# gsm.net
KiCad netlist of a schematic drawn in Altium Designer
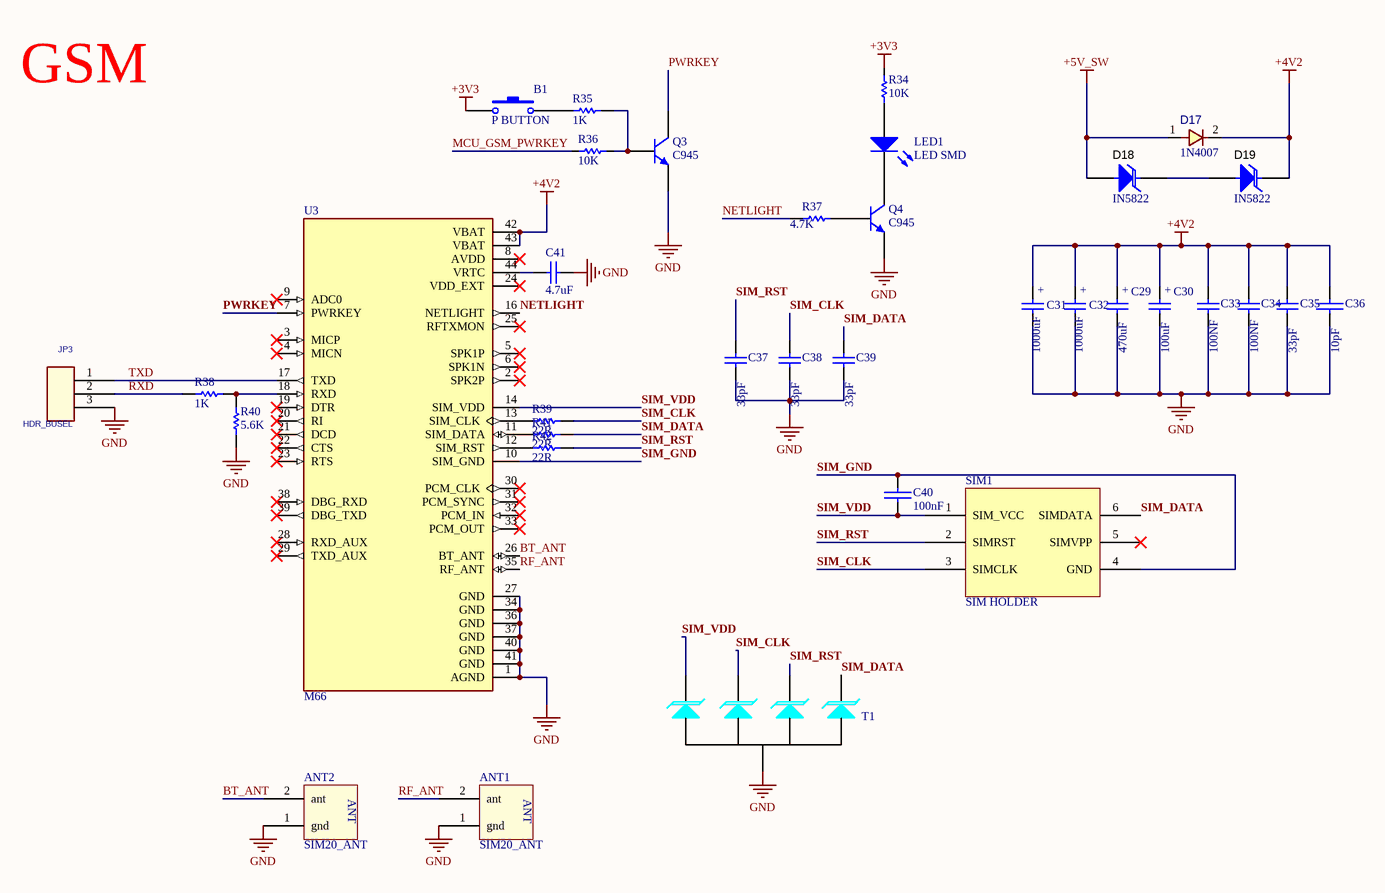
[diagram p0: gsm.SchDoc]

(export (version "E")
  (design (tool "Eeschema 10.0.6"))
  (components
    (comp (ref "ANT1")
      (value "SIM20_ANT")
      (footprint "MY_SIM20_ANT")
      (description "ANT")
      (libsource (lib "altium-import") (part "root_2_SIM20_ANT_"))
    )
    (comp (ref "ANT2")
      (value "SIM20_ANT")
      (footprint "MY_SIM20_ANT")
      (description "ANT")
      (libsource (lib "altium-import") (part "root_2_SIM20_ANT_"))
    )
    (comp (ref "B1")
      (value "P BUTTON")
      (footprint "MY_SPST-0.5")
      (libsource (lib "AMINLIB") (part "PUSH BUTTON_SMALL"))
    )
    (comp (ref "C29")
      (value "470uF")
      (footprint "MY_Cap1000u -smd")
      (description "aluminium")
      (libsource (lib "AMINLIB") (part "cap_smd_1000u_smd G"))
    )
    (comp (ref "C30")
      (value "100uF")
      (footprint "MY_Cap1000u -smd")
      (description "aluminium")
      (libsource (lib "AMINLIB") (part "cap_smd_1000u_smd G"))
    )
    (comp (ref "C31")
      (value "1000uF")
      (footprint "MY_CAP_SMD-C")
      (description "6X3.2MM")
      (libsource (lib "altium-import") (part "root_3_CAP_TANTAL_C_"))
    )
    (comp (ref "C32")
      (value "1000uF")
      (footprint "MY_CAP_SMD-C")
      (description "6X3.2MM")
      (libsource (lib "altium-import") (part "root_3_CAP_TANTAL_C_"))
    )
    (comp (ref "C33")
      (value "100NF")
      (footprint "CAP0603")
      (description "TOTAL CAPACITOR SMD PACK")
      (fields (field (name "DESIGNER") "Abbas Basereh"))
      (libsource (lib "Altium") (part "CAP SMD PACKAGE"))
    )
    (comp (ref "C34")
      (value "100NF")
      (footprint "CAP0603")
      (description "TOTAL CAPACITOR SMD PACK")
      (fields (field (name "DESIGNER") "Abbas Basereh"))
      (libsource (lib "Altium") (part "CAP SMD PACKAGE"))
    )
    (comp (ref "C35")
      (value "33pF")
      (footprint "CAP0603")
      (description "TOTAL CAPACITOR SMD PACK")
      (fields (field (name "DESIGNER") "Abbas Basereh"))
      (libsource (lib "Altium") (part "CAP SMD PACKAGE"))
    )
    (comp (ref "C36")
      (value "10pF")
      (footprint "Cap-0603")
      (description "Capacitor")
      (fields (field (name "PUBLISHER") "Altium Limited"))
      (libsource (lib "A.Mohebbi") (part "Capacitor."))
    )
    (comp (ref "C37")
      (value "33pF")
      (footprint "CAP0603")
      (description "TOTAL CAPACITOR SMD PACK")
      (fields (field (name "DESIGNER") "Abbas Basereh"))
      (libsource (lib "Altium") (part "CAP SMD PACKAGE"))
    )
    (comp (ref "C38")
      (value "33pF")
      (footprint "CAP0603")
      (description "TOTAL CAPACITOR SMD PACK")
      (fields (field (name "DESIGNER") "Abbas Basereh"))
      (libsource (lib "Altium") (part "CAP SMD PACKAGE"))
    )
    (comp (ref "C39")
      (value "33pF")
      (footprint "CAP0603")
      (description "TOTAL CAPACITOR SMD PACK")
      (fields (field (name "DESIGNER") "Abbas Basereh"))
      (libsource (lib "Altium") (part "CAP SMD PACKAGE"))
    )
    (comp (ref "C40")
      (value "100nF")
      (footprint "Cap-0805")
      (description "Capacitor")
      (fields (field (name "PUBLISHER") "Altium Limited"))
      (libsource (lib "altium-import") (part "root_0_Capacitor._"))
    )
    (comp (ref "C41")
      (value "4.7uF")
      (footprint "CAPC3413X12N")
      (description "CAP 0805")
      (fields (field (name "DESIGNER") "Abbas Basereh"))
      (libsource (lib "2017AbbasBasereh9365731239 -ver1") (part "CAP SMD 0805"))
    )
    (comp (ref "D17")
      (value "1N4007")
      (footprint "D_SMA")
      (description "DIODE, GENERAL PURPOSE, 1000V/1A")
      (fields (field (name "Comment") "1N4007 SMD M7"))
      (libsource (lib "Diode") (part "1N4007 SMD M7"))
    )
    (comp (ref "D18")
      (value "IN5822")
      (footprint "BYW98")
      (description "Diode, , 20 - 40V, 3.0 A")
      (fields (field (name "Comment") "IN5822 THD"))
      (libsource (lib "altium-import") (part "root_2_IN5822 THD_"))
    )
    (comp (ref "D19")
      (value "IN5822")
      (footprint "BYW98")
      (description "Diode, , 20 - 40V, 3.0 A")
      (fields (field (name "Comment") "IN5822 THD"))
      (libsource (lib "altium-import") (part "root_2_IN5822 THD_"))
    )
    (comp (ref "JP3")
      (value "HDR_BUSEL")
      (footprint "HDR_1x3")
      (description "header or jumper box")
      (libsource (lib "2017AbbasBasereh9365731239 -ver1") (part "Header 1x3"))
    )
    (comp (ref "LED1")
      (value "LED SMD")
      (footprint "MY_LED_SMD")
      (libsource (lib "AMINLIB") (part "LED SMD"))
    )
    (comp (ref "Q3")
      (value "C945")
      (footprint "SOT23_N")
      (description "NPN Silicon Epitaxial Planar Transistor")
      (fields (field (name "PUBLISHER") "Abbas Basereh"))
      (libsource (lib "2017AbbasBasereh9365731239 -ver1") (part "C945"))
    )
    (comp (ref "Q4")
      (value "C945")
      (footprint "SOT23_N")
      (description "NPN Silicon Epitaxial Planar Transistor")
      (fields (field (name "PUBLISHER") "Abbas Basereh"))
      (libsource (lib "2017AbbasBasereh9365731239 -ver1") (part "C945"))
    )
    (comp (ref "R34")
      (value "10K")
      (footprint "RES 0603 (1608X06L)")
      (description "Resistor")
      (fields (field (name "TOLERANCE") "5%") (field (name "POWER") "1/4 W"))
      (libsource (lib "altium-import") (part "root_1_Resistor_"))
    )
    (comp (ref "R35")
      (value "1K")
      (footprint "Resistor_SMD_1206 (3216)")
      (description "Resistor")
      (fields (field (name "PUBLISHER") "Seyed Razi Vesali") (field (name "EMAIL") "razi.vesali@gmail.com"))
      (libsource (lib "resistors") (part "Resistor"))
    )
    (comp (ref "R36")
      (value "10K")
      (footprint "RES 0603 (1608X06L)")
      (description "Resistor")
      (fields (field (name "TOLERANCE") "5%") (field (name "POWER") "1/4 W"))
      (libsource (lib "altium-import") (part "root_0_Resistor_"))
    )
    (comp (ref "R37")
      (value "4.7K")
      (footprint "Resistor_SMD_1206")
      (description "Resistor 0.25w")
      (fields (field (name "PUBLISHER") "Altium Limited"))
      (libsource (lib "A.Mohebbi") (part "Resistor"))
    )
    (comp (ref "R38")
      (value "1K")
      (footprint "Resistor_SMD_1206 (3216)")
      (description "Resistor")
      (fields (field (name "PUBLISHER") "Seyed Razi Vesali") (field (name "EMAIL") "razi.vesali@gmail.com"))
      (libsource (lib "resistors") (part "Resistor"))
    )
    (comp (ref "R39")
      (value "22R")
      (footprint "Resistor_SMD_0603 (1608)")
      (description "Resistor")
      (fields (field (name "PUBLISHER") "Seyed Razi Vesali") (field (name "EMAIL") "razi.vesali@gmail.com"))
      (libsource (lib "resistors") (part "Resistor"))
    )
    (comp (ref "R40")
      (value "5.6K")
      (footprint "Resistor_SMD_0805 (2012)")
      (description "Resistor")
      (fields (field (name "PUBLISHER") "Seyed Razi Vesali") (field (name "EMAIL") "razi.vesali@gmail.com"))
      (libsource (lib "resistors") (part "Resistor"))
    )
    (comp (ref "R41")
      (value "22R")
      (footprint "Resistor_SMD_0603 (1608)")
      (description "Resistor")
      (fields (field (name "PUBLISHER") "Seyed Razi Vesali") (field (name "EMAIL") "razi.vesali@gmail.com"))
      (libsource (lib "resistors") (part "Resistor"))
    )
    (comp (ref "R42")
      (value "22R")
      (footprint "Resistor_SMD_0603 (1608)")
      (description "Resistor")
      (fields (field (name "PUBLISHER") "Seyed Razi Vesali") (field (name "EMAIL") "razi.vesali@gmail.com"))
      (libsource (lib "resistors") (part "Resistor"))
    )
    (comp (ref "SIM1")
      (value "SIM HOLDER")
      (footprint "SIM HOLDER 6")
      (libsource (lib "altium-import") (part "root_0_SIM HOLDER_"))
    )
    (comp (ref "T1")
      (value "TVS (SMF05)")
      (footprint "SC70-5L")
      (description "SMF05 and SMF12  TVS Diode Array  For ESD and Latch-Up Protection")
      (libsource (lib "altium-import") (part "root_0_TVS (SMF05)_"))
    )
    (comp (ref "U3")
      (value "M66")
      (footprint "XCVR_M66")
      (fields (field (name "MF") "Quectel"))
      (libsource (lib "M66") (part "M66"))
    )
  )
  (nets
    (net (code "1") (name "+3V3") (class "Default")
      (node (ref "B1") (pin "1") (pinfunction "1_1") (pintype "passive"))
      (node (ref "R34") (pin "2") (pinfunction "2_2") (pintype "passive"))
    )
    (net (code "2") (name "+4V2") (class "Default")
      (node (ref "C29") (pin "+") (pinfunction "+_+") (pintype "passive"))
      (node (ref "C30") (pin "+") (pinfunction "+_+") (pintype "passive"))
      (node (ref "C31") (pin "+") (pinfunction "+_+") (pintype "passive"))
      (node (ref "C32") (pin "+") (pinfunction "+_+") (pintype "passive"))
      (node (ref "C33") (pin "2") (pinfunction "2_2") (pintype "passive"))
      (node (ref "C34") (pin "2") (pinfunction "2_2") (pintype "passive"))
      (node (ref "C35") (pin "2") (pinfunction "2_2") (pintype "passive"))
      (node (ref "C36") (pin "1") (pinfunction "1_1") (pintype "passive"))
      (node (ref "D17") (pin "2") (pinfunction "2_2") (pintype "passive"))
      (node (ref "D19") (pin "2") (pinfunction "K_2") (pintype "passive"))
      (node (ref "U3") (pin "42") (pinfunction "VBAT_42") (pintype "power_in"))
      (node (ref "U3") (pin "43") (pinfunction "VBAT_43") (pintype "power_in"))
    )
    (net (code "3") (name "+5V_SW") (class "Default")
      (node (ref "D17") (pin "1") (pinfunction "1_1") (pintype "passive"))
      (node (ref "D18") (pin "1") (pinfunction "A_1") (pintype "passive"))
    )
    (net (code "4") (name "/BT_ANT") (class "Default")
      (node (ref "ANT2") (pin "2") (pinfunction "ant_2") (pintype "passive"))
      (node (ref "U3") (pin "26") (pinfunction "BT_ANT_26") (pintype "bidirectional"))
    )
    (net (code "5") (name "/MCU_GSM_PWRKEY") (class "Default")
      (node (ref "R36") (pin "1") (pinfunction "1_1") (pintype "passive"))
    )
    (net (code "6") (name "/NETLIGHT") (class "Default")
      (node (ref "R37") (pin "1") (pinfunction "1_1") (pintype "passive"))
      (node (ref "U3") (pin "16") (pinfunction "NETLIGHT_16") (pintype "output"))
    )
    (net (code "7") (name "/PWRKEY") (class "Default")
      (node (ref "Q3") (pin "3") (pinfunction "C_3") (pintype "passive"))
      (node (ref "U3") (pin "7") (pinfunction "PWRKEY_7") (pintype "input"))
    )
    (net (code "8") (name "/RF_ANT") (class "Default")
      (node (ref "ANT1") (pin "2") (pinfunction "ant_2") (pintype "passive"))
      (node (ref "U3") (pin "35") (pinfunction "RF_ANT_35") (pintype "bidirectional"))
    )
    (net (code "9") (name "/RXD") (class "Default")
      (node (ref "JP3") (pin "2") (pinfunction "2_2") (pintype "passive"))
      (node (ref "R38") (pin "1") (pinfunction "1_1") (pintype "passive"))
    )
    (net (code "10") (name "/SIM_CLK") (class "Default")
      (node (ref "C38") (pin "2") (pinfunction "2_2") (pintype "passive"))
      (node (ref "R39") (pin "2") (pinfunction "2_2") (pintype "passive"))
      (node (ref "SIM1") (pin "3") (pinfunction "SIMCLK_3") (pintype "passive"))
      (node (ref "T1") (pin "3") (pinfunction "K_3") (pintype "passive"))
    )
    (net (code "11") (name "/SIM_DATA") (class "Default")
      (node (ref "C39") (pin "2") (pinfunction "2_2") (pintype "passive"))
      (node (ref "R41") (pin "2") (pinfunction "2_2") (pintype "passive"))
      (node (ref "SIM1") (pin "6") (pinfunction "SIMDATA_6") (pintype "passive"))
      (node (ref "T1") (pin "5") (pinfunction "K_5") (pintype "passive"))
    )
    (net (code "12") (name "/SIM_GND") (class "Default")
      (node (ref "C40") (pin "1") (pinfunction "1_1") (pintype "passive"))
      (node (ref "SIM1") (pin "4") (pinfunction "GND_4") (pintype "passive"))
      (node (ref "U3") (pin "10") (pinfunction "SIM_GND_10") (pintype "power_in"))
    )
    (net (code "13") (name "/SIM_RST") (class "Default")
      (node (ref "C37") (pin "2") (pinfunction "2_2") (pintype "passive"))
      (node (ref "R42") (pin "2") (pinfunction "2_2") (pintype "passive"))
      (node (ref "SIM1") (pin "2") (pinfunction "SIMRST_2") (pintype "passive"))
      (node (ref "T1") (pin "4") (pinfunction "K_4") (pintype "passive"))
    )
    (net (code "14") (name "/SIM_VDD") (class "Default")
      (node (ref "C40") (pin "2") (pinfunction "2_2") (pintype "passive"))
      (node (ref "SIM1") (pin "1") (pinfunction "SIM_VCC_1") (pintype "passive"))
      (node (ref "T1") (pin "1") (pinfunction "K_1") (pintype "passive"))
      (node (ref "U3") (pin "14") (pinfunction "SIM_VDD_14") (pintype "power_in"))
    )
    (net (code "15") (name "/TXD") (class "Default")
      (node (ref "JP3") (pin "1") (pinfunction "1_1") (pintype "passive"))
      (node (ref "U3") (pin "17") (pinfunction "TXD_17") (pintype "output"))
    )
    (net (code "16") (name "GND") (class "Default")
      (node (ref "ANT1") (pin "1") (pinfunction "gnd_1") (pintype "passive"))
      (node (ref "ANT2") (pin "1") (pinfunction "gnd_1") (pintype "passive"))
      (node (ref "C29") (pin "-") (pinfunction "-_-") (pintype "passive"))
      (node (ref "C30") (pin "-") (pinfunction "-_-") (pintype "passive"))
      (node (ref "C31") (pin "-") (pinfunction "-_-") (pintype "passive"))
      (node (ref "C32") (pin "-") (pinfunction "-_-") (pintype "passive"))
      (node (ref "C33") (pin "1") (pinfunction "1_1") (pintype "passive"))
      (node (ref "C34") (pin "1") (pinfunction "1_1") (pintype "passive"))
      (node (ref "C35") (pin "1") (pinfunction "1_1") (pintype "passive"))
      (node (ref "C36") (pin "2") (pinfunction "2_2") (pintype "passive"))
      (node (ref "C37") (pin "1") (pinfunction "1_1") (pintype "passive"))
      (node (ref "C38") (pin "1") (pinfunction "1_1") (pintype "passive"))
      (node (ref "C39") (pin "1") (pinfunction "1_1") (pintype "passive"))
      (node (ref "C41") (pin "2") (pinfunction "2_2") (pintype "passive"))
      (node (ref "JP3") (pin "3") (pinfunction "3_3") (pintype "passive"))
      (node (ref "Q3") (pin "2") (pinfunction "E_2") (pintype "passive"))
      (node (ref "Q4") (pin "2") (pinfunction "E_2") (pintype "passive"))
      (node (ref "R40") (pin "1") (pinfunction "1_1") (pintype "passive"))
      (node (ref "T1") (pin "2") (pinfunction "A_2") (pintype "passive"))
      (node (ref "U3") (pin "1") (pinfunction "AGND_1") (pintype "power_in"))
      (node (ref "U3") (pin "27") (pinfunction "GND_27") (pintype "power_in"))
      (node (ref "U3") (pin "34") (pinfunction "GND_34") (pintype "power_in"))
      (node (ref "U3") (pin "36") (pinfunction "GND_36") (pintype "power_in"))
      (node (ref "U3") (pin "37") (pinfunction "GND_37") (pintype "power_in"))
      (node (ref "U3") (pin "40") (pinfunction "GND_40") (pintype "power_in"))
      (node (ref "U3") (pin "41") (pinfunction "GND_41") (pintype "power_in"))
    )
    (net (code "17") (name "Net-(B1-Pad2)") (class "Default")
      (node (ref "B1") (pin "2") (pinfunction "2_2") (pintype "passive"))
      (node (ref "R35") (pin "1") (pinfunction "1_1") (pintype "passive"))
    )
    (net (code "18") (name "Net-(D18-K)") (class "Default")
      (node (ref "D18") (pin "2") (pinfunction "K_2") (pintype "passive"))
      (node (ref "D19") (pin "1") (pinfunction "A_1") (pintype "passive"))
    )
    (net (code "19") (name "Net-(LED1-A)") (class "Default")
      (node (ref "LED1") (pin "1") (pinfunction "A_1") (pintype "passive"))
      (node (ref "R34") (pin "1") (pinfunction "1_1") (pintype "passive"))
    )
    (net (code "20") (name "Net-(LED1-K)") (class "Default")
      (node (ref "LED1") (pin "2") (pinfunction "K_2") (pintype "passive"))
      (node (ref "Q4") (pin "3") (pinfunction "C_3") (pintype "passive"))
    )
    (net (code "21") (name "Net-(Q3-B)") (class "Default")
      (node (ref "Q3") (pin "1") (pinfunction "B_1") (pintype "passive"))
      (node (ref "R35") (pin "2") (pinfunction "2_2") (pintype "passive"))
      (node (ref "R36") (pin "2") (pinfunction "2_2") (pintype "passive"))
    )
    (net (code "22") (name "Net-(Q4-B)") (class "Default")
      (node (ref "Q4") (pin "1") (pinfunction "B_1") (pintype "passive"))
      (node (ref "R37") (pin "2") (pinfunction "2_2") (pintype "passive"))
    )
    (net (code "23") (name "Net-(U3-RXD)") (class "Default")
      (node (ref "R38") (pin "2") (pinfunction "2_2") (pintype "passive"))
      (node (ref "R40") (pin "2") (pinfunction "2_2") (pintype "passive"))
      (node (ref "U3") (pin "18") (pinfunction "RXD_18") (pintype "input"))
    )
    (net (code "24") (name "Net-(U3-SIM_CLK)") (class "Default")
      (node (ref "R39") (pin "1") (pinfunction "1_1") (pintype "passive"))
      (node (ref "U3") (pin "13") (pinfunction "SIM_CLK_13") (pintype "output"))
    )
    (net (code "25") (name "Net-(U3-SIM_DATA)") (class "Default")
      (node (ref "R41") (pin "1") (pinfunction "1_1") (pintype "passive"))
      (node (ref "U3") (pin "11") (pinfunction "SIM_DATA_11") (pintype "bidirectional"))
    )
    (net (code "26") (name "Net-(U3-SIM_RST)") (class "Default")
      (node (ref "R42") (pin "1") (pinfunction "1_1") (pintype "passive"))
      (node (ref "U3") (pin "12") (pinfunction "SIM_RST_12") (pintype "output"))
    )
    (net (code "27") (name "Net-(U3-VRTC)") (class "Default")
      (node (ref "C41") (pin "1") (pinfunction "1_1") (pintype "passive"))
      (node (ref "U3") (pin "44") (pinfunction "VRTC_44") (pintype "power_in"))
    )
    (net (code "28") (name "unconnected-(SIM1-SIMVPP-Pad5)") (class "Default")
      (node (ref "SIM1") (pin "5") (pinfunction "SIMVPP_5") (pintype "passive+no_connect"))
    )
    (net (code "29") (name "unconnected-(U3-ADC0-Pad9)") (class "Default")
      (node (ref "U3") (pin "9") (pinfunction "ADC0_9") (pintype "input+no_connect"))
    )
    (net (code "30") (name "unconnected-(U3-AVDD-Pad8)") (class "Default")
      (node (ref "U3") (pin "8") (pinfunction "AVDD_8") (pintype "power_in+no_connect"))
    )
    (net (code "31") (name "unconnected-(U3-CTS-Pad22)") (class "Default")
      (node (ref "U3") (pin "22") (pinfunction "CTS_22") (pintype "output+no_connect"))
    )
    (net (code "32") (name "unconnected-(U3-DBG_RXD-Pad38)") (class "Default")
      (node (ref "U3") (pin "38") (pinfunction "DBG_RXD_38") (pintype "input+no_connect"))
    )
    (net (code "33") (name "unconnected-(U3-DBG_TXD-Pad39)") (class "Default")
      (node (ref "U3") (pin "39") (pinfunction "DBG_TXD_39") (pintype "output+no_connect"))
    )
    (net (code "34") (name "unconnected-(U3-DCD-Pad21)") (class "Default")
      (node (ref "U3") (pin "21") (pinfunction "DCD_21") (pintype "output+no_connect"))
    )
    (net (code "35") (name "unconnected-(U3-DTR-Pad19)") (class "Default")
      (node (ref "U3") (pin "19") (pinfunction "DTR_19") (pintype "input+no_connect"))
    )
    (net (code "36") (name "unconnected-(U3-MICN-Pad4)") (class "Default")
      (node (ref "U3") (pin "4") (pinfunction "MICN_4") (pintype "input+no_connect"))
    )
    (net (code "37") (name "unconnected-(U3-MICP-Pad3)") (class "Default")
      (node (ref "U3") (pin "3") (pinfunction "MICP_3") (pintype "input+no_connect"))
    )
    (net (code "38") (name "unconnected-(U3-PCM_CLK-Pad30)") (class "Default")
      (node (ref "U3") (pin "30") (pinfunction "PCM_CLK_30") (pintype "output+no_connect"))
    )
    (net (code "39") (name "unconnected-(U3-PCM_IN-Pad32)") (class "Default")
      (node (ref "U3") (pin "32") (pinfunction "PCM_IN_32") (pintype "input+no_connect"))
    )
    (net (code "40") (name "unconnected-(U3-PCM_OUT-Pad33)") (class "Default")
      (node (ref "U3") (pin "33") (pinfunction "PCM_OUT_33") (pintype "output+no_connect"))
    )
    (net (code "41") (name "unconnected-(U3-PCM_SYNC-Pad31)") (class "Default")
      (node (ref "U3") (pin "31") (pinfunction "PCM_SYNC_31") (pintype "output+no_connect"))
    )
    (net (code "42") (name "unconnected-(U3-RFTXMON-Pad25)") (class "Default")
      (node (ref "U3") (pin "25") (pinfunction "RFTXMON_25") (pintype "output+no_connect"))
    )
    (net (code "43") (name "unconnected-(U3-RI-Pad20)") (class "Default")
      (node (ref "U3") (pin "20") (pinfunction "RI_20") (pintype "output+no_connect"))
    )
    (net (code "44") (name "unconnected-(U3-RTS-Pad23)") (class "Default")
      (node (ref "U3") (pin "23") (pinfunction "RTS_23") (pintype "input+no_connect"))
    )
    (net (code "45") (name "unconnected-(U3-RXD_AUX-Pad28)") (class "Default")
      (node (ref "U3") (pin "28") (pinfunction "RXD_AUX_28") (pintype "input+no_connect"))
    )
    (net (code "46") (name "unconnected-(U3-SPK1N-Pad6)") (class "Default")
      (node (ref "U3") (pin "6") (pinfunction "SPK1N_6") (pintype "output+no_connect"))
    )
    (net (code "47") (name "unconnected-(U3-SPK1P-Pad5)") (class "Default")
      (node (ref "U3") (pin "5") (pinfunction "SPK1P_5") (pintype "output+no_connect"))
    )
    (net (code "48") (name "unconnected-(U3-SPK2P-Pad2)") (class "Default")
      (node (ref "U3") (pin "2") (pinfunction "SPK2P_2") (pintype "output+no_connect"))
    )
    (net (code "49") (name "unconnected-(U3-TXD_AUX-Pad29)") (class "Default")
      (node (ref "U3") (pin "29") (pinfunction "TXD_AUX_29") (pintype "output+no_connect"))
    )
    (net (code "50") (name "unconnected-(U3-VDD_EXT-Pad24)") (class "Default")
      (node (ref "U3") (pin "24") (pinfunction "VDD_EXT_24") (pintype "power_in+no_connect"))
    )
  )
)
